# Brians_test_board_1_18.net
KiCad netlist of a schematic drawn in EAGLE
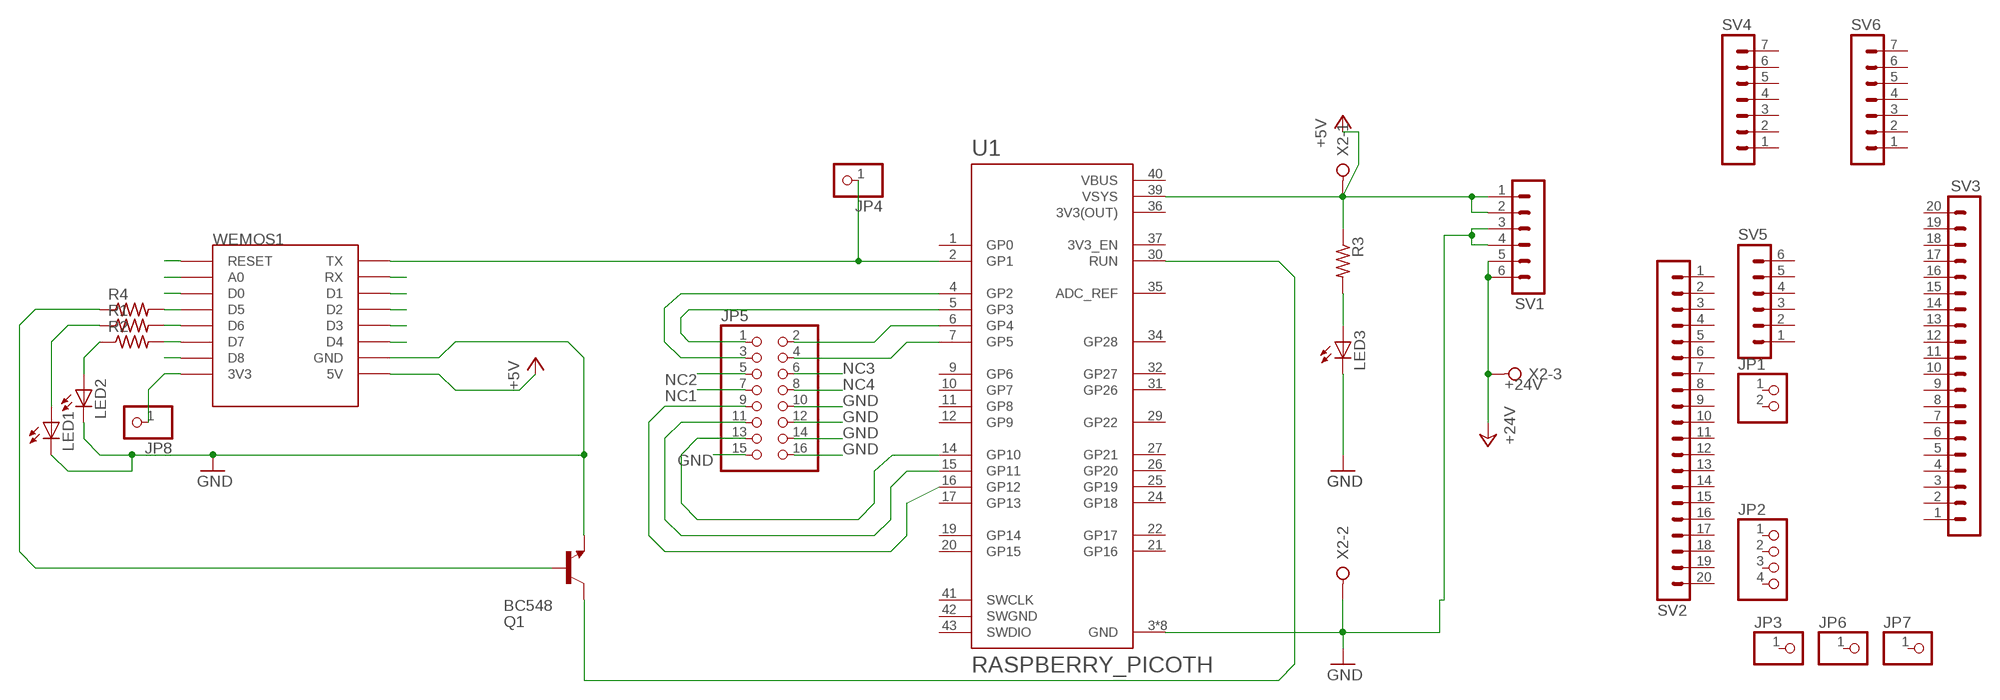
[diagram p0: schematic, sheet 1]

(export (version "E")
  (design (tool "Eeschema 10.0.6"))
  (components
    (comp (ref "JP1")
      (value "PINHD-1X2")
      (footprint "eagle-import:1X02")
      (libsource (lib "eagle-import") (part "PINHD-1X2"))
    )
    (comp (ref "JP2")
      (value "PINHD-1X4")
      (footprint "eagle-import:1X04")
      (libsource (lib "eagle-import") (part "PINHD-1X4"))
    )
    (comp (ref "JP3")
      (value "PINHD-1X1")
      (footprint "eagle-import:1X01")
      (libsource (lib "eagle-import") (part "PINHD-1X1"))
    )
    (comp (ref "JP4")
      (value "PINHD-1X1")
      (footprint "eagle-import:1X01")
      (libsource (lib "eagle-import") (part "PINHD-1X1"))
    )
    (comp (ref "JP5")
      (value "PINHD-2X8")
      (footprint "eagle-import:2X08")
      (libsource (lib "eagle-import") (part "PINHD-2X8"))
    )
    (comp (ref "JP6")
      (value "PINHD-1X1")
      (footprint "eagle-import:1X01")
      (libsource (lib "eagle-import") (part "PINHD-1X1"))
    )
    (comp (ref "JP7")
      (value "PINHD-1X1")
      (footprint "eagle-import:1X01")
      (libsource (lib "eagle-import") (part "PINHD-1X1"))
    )
    (comp (ref "JP8")
      (value "PINHD-1X1")
      (footprint "eagle-import:1X01")
      (libsource (lib "eagle-import") (part "PINHD-1X1"))
    )
    (comp (ref "LED1")
      (value "LED3MM")
      (footprint "eagle-import:LED3MM")
      (libsource (lib "eagle-import") (part "LED3MM"))
    )
    (comp (ref "LED2")
      (value "LED3MM")
      (footprint "eagle-import:LED3MM")
      (libsource (lib "eagle-import") (part "LED3MM"))
    )
    (comp (ref "LED3")
      (value "LED3MM")
      (footprint "eagle-import:LED3MM")
      (libsource (lib "eagle-import") (part "LED3MM"))
    )
    (comp (ref "Q1")
      (value "BC548")
      (footprint "eagle-import:TO92-EBC")
      (libsource (lib "eagle-import") (part "BC548"))
    )
    (comp (ref "R1")
      (value "R-US_0204/2V")
      (footprint "eagle-import:0204V")
      (libsource (lib "eagle-import") (part "R-US_0204/2V"))
    )
    (comp (ref "R2")
      (value "R-US_0204/2V")
      (footprint "eagle-import:0204V")
      (libsource (lib "eagle-import") (part "R-US_0204/2V"))
    )
    (comp (ref "R3")
      (value "R-US_0207/10")
      (footprint "eagle-import:0207_10")
      (libsource (lib "eagle-import") (part "R-US_0207/10"))
    )
    (comp (ref "R4")
      (value "R-US_0204/2V")
      (footprint "eagle-import:0204V")
      (libsource (lib "eagle-import") (part "R-US_0204/2V"))
    )
    (comp (ref "SV1")
      (value "MA06-1")
      (footprint "eagle-import:MA06-1")
      (libsource (lib "eagle-import") (part "MA06-1"))
    )
    (comp (ref "SV2")
      (value "MA20-1")
      (footprint "eagle-import:MA20-1")
      (libsource (lib "eagle-import") (part "MA20-1"))
    )
    (comp (ref "SV3")
      (value "MA20-1")
      (footprint "eagle-import:MA20-1")
      (libsource (lib "eagle-import") (part "MA20-1"))
    )
    (comp (ref "SV4")
      (value "MA07-1")
      (footprint "eagle-import:MA07-1")
      (libsource (lib "eagle-import") (part "MA07-1"))
    )
    (comp (ref "SV5")
      (value "MA06-1")
      (footprint "eagle-import:MA06-1")
      (libsource (lib "eagle-import") (part "MA06-1"))
    )
    (comp (ref "SV6")
      (value "MA07-1")
      (footprint "eagle-import:MA07-1")
      (libsource (lib "eagle-import") (part "MA07-1"))
    )
    (comp (ref "U1")
      (value "RASPBERRY_PICOTH")
      (footprint "eagle-import:PICO-PKG-TH")
      (libsource (lib "eagle-import") (part "RASPBERRY_PICOTH"))
    )
    (comp (ref "WEMOS1")
      (value "WEMOS-D1-MINI")
      (footprint "eagle-import:WEMOS-D1-MINI")
      (libsource (lib "eagle-import") (part "WEMOS-D1-MINI"))
    )
    (comp (ref "X2")
      (value "W237-3E")
      (footprint "eagle-import:W237-3E")
      (libsource (lib "eagle-import") (part "W237-3E"))
    )
  )
  (nets
    (net (code "1") (name "+5V") (class "Default")
      (node (ref "R3") (pin "1") (pinfunction "1_1") (pintype "passive"))
      (node (ref "SV1") (pin "1") (pinfunction "1_1") (pintype "passive"))
      (node (ref "SV1") (pin "2") (pinfunction "2_2") (pintype "passive"))
      (node (ref "U1") (pin "39") (pinfunction "VSYS_39") (pintype "power_in"))
      (node (ref "WEMOS1") (pin "5V") (pinfunction "5V_5V") (pintype "bidirectional"))
      (node (ref "X2") (pin "1") (pinfunction "KL_1") (pintype "passive"))
    )
    (net (code "2") (name "+24V") (class "Default")
      (node (ref "SV1") (pin "5") (pinfunction "5_5") (pintype "passive"))
      (node (ref "SV1") (pin "6") (pinfunction "6_6") (pintype "passive"))
      (node (ref "X2") (pin "3") (pinfunction "KL_3") (pintype "passive"))
    )
    (net (code "3") (name "/3V3(OUT)") (class "Default")
      (node (ref "U1") (pin "36") (pinfunction "3V3(OUT)_36") (pintype "power_in"))
    )
    (net (code "4") (name "/NC1") (class "Default")
      (node (ref "JP5") (pin "7") (pinfunction "7_7") (pintype "passive"))
    )
    (net (code "5") (name "/NC2") (class "Default")
      (node (ref "JP5") (pin "5") (pinfunction "5_5") (pintype "passive"))
    )
    (net (code "6") (name "/NC3") (class "Default")
      (node (ref "JP5") (pin "6") (pinfunction "6_6") (pintype "passive"))
    )
    (net (code "7") (name "/NC4") (class "Default")
      (node (ref "JP5") (pin "8") (pinfunction "8_8") (pintype "passive"))
    )
    (net (code "8") (name "/SWGND") (class "Default")
      (node (ref "U1") (pin "42") (pinfunction "SWGND_42") (pintype "power_in"))
    )
    (net (code "9") (name "/VBUS") (class "Default")
      (node (ref "U1") (pin "40") (pinfunction "VBUS_40") (pintype "power_in"))
    )
    (net (code "10") (name "GND") (class "Default")
      (node (ref "JP5") (pin "10") (pinfunction "10_10") (pintype "passive"))
      (node (ref "JP5") (pin "12") (pinfunction "12_12") (pintype "passive"))
      (node (ref "JP5") (pin "14") (pinfunction "14_14") (pintype "passive"))
      (node (ref "JP5") (pin "15") (pinfunction "15_15") (pintype "passive"))
      (node (ref "JP5") (pin "16") (pinfunction "16_16") (pintype "passive"))
      (node (ref "LED1") (pin "K") (pinfunction "C_K") (pintype "passive"))
      (node (ref "LED2") (pin "K") (pinfunction "C_K") (pintype "passive"))
      (node (ref "LED3") (pin "K") (pinfunction "C_K") (pintype "passive"))
      (node (ref "Q1") (pin "E") (pinfunction "E_E") (pintype "passive"))
      (node (ref "SV1") (pin "3") (pinfunction "3_3") (pintype "passive"))
      (node (ref "SV1") (pin "4") (pinfunction "4_4") (pintype "passive"))
      (node (ref "U1") (pin "13") (pinfunction "GND_13") (pintype "power_in"))
      (node (ref "U1") (pin "18") (pinfunction "GND_18") (pintype "power_in"))
      (node (ref "U1") (pin "23") (pinfunction "GND_23") (pintype "power_in"))
      (node (ref "U1") (pin "28") (pinfunction "GND_28") (pintype "power_in"))
      (node (ref "U1") (pin "3") (pinfunction "GND_3") (pintype "power_in"))
      (node (ref "U1") (pin "33") (pinfunction "GND_33") (pintype "power_in"))
      (node (ref "U1") (pin "38") (pinfunction "GND_38") (pintype "power_in"))
      (node (ref "U1") (pin "8") (pinfunction "GND_8") (pintype "power_in"))
      (node (ref "WEMOS1") (pin "GND") (pinfunction "GND_GND") (pintype "bidirectional"))
      (node (ref "X2") (pin "2") (pinfunction "KL_2") (pintype "passive"))
    )
    (net (code "11") (name "Net-(JP8-Pad1)") (class "Default")
      (node (ref "JP8") (pin "1") (pinfunction "1_1") (pintype "passive"))
      (node (ref "WEMOS1") (pin "3V3") (pinfunction "3V3_3V3") (pintype "bidirectional"))
    )
    (net (code "12") (name "Net-(LED1-PadA)") (class "Default")
      (node (ref "LED1") (pin "A") (pinfunction "A_A") (pintype "passive"))
      (node (ref "R1") (pin "1") (pinfunction "1_1") (pintype "passive"))
    )
    (net (code "13") (name "Net-(LED2-PadA)") (class "Default")
      (node (ref "LED2") (pin "A") (pinfunction "A_A") (pintype "passive"))
      (node (ref "R2") (pin "1") (pinfunction "1_1") (pintype "passive"))
    )
    (net (code "14") (name "Net-(LED3-PadA)") (class "Default")
      (node (ref "LED3") (pin "A") (pinfunction "A_A") (pintype "passive"))
      (node (ref "R3") (pin "2") (pinfunction "2_2") (pintype "passive"))
    )
    (net (code "15") (name "Net-(Q1-PadB)") (class "Default")
      (node (ref "Q1") (pin "B") (pinfunction "B_B") (pintype "passive"))
      (node (ref "R4") (pin "1") (pinfunction "1_1") (pintype "passive"))
    )
    (net (code "16") (name "Net-(R1-Pad2)") (class "Default")
      (node (ref "R1") (pin "2") (pinfunction "2_2") (pintype "passive"))
      (node (ref "WEMOS1") (pin "D6") (pinfunction "D6_D6") (pintype "bidirectional"))
    )
    (net (code "17") (name "Net-(R2-Pad2)") (class "Default")
      (node (ref "R2") (pin "2") (pinfunction "2_2") (pintype "passive"))
      (node (ref "WEMOS1") (pin "D7") (pinfunction "D7_D7") (pintype "bidirectional"))
    )
    (net (code "18") (name "Net-(R4-Pad2)") (class "Default")
      (node (ref "R4") (pin "2") (pinfunction "2_2") (pintype "passive"))
      (node (ref "WEMOS1") (pin "D5") (pinfunction "D5_D5") (pintype "bidirectional"))
    )
    (net (code "19") (name "Net-(U1-GP1)") (class "Default")
      (node (ref "JP4") (pin "1") (pinfunction "1_1") (pintype "passive"))
      (node (ref "U1") (pin "2") (pinfunction "GP1_2") (pintype "bidirectional"))
      (node (ref "WEMOS1") (pin "TX") (pinfunction "TX_TX") (pintype "bidirectional"))
    )
    (net (code "20") (name "Net-(U1-GP2)") (class "Default")
      (node (ref "JP5") (pin "3") (pinfunction "3_3") (pintype "passive"))
      (node (ref "U1") (pin "4") (pinfunction "GP2_4") (pintype "bidirectional"))
    )
    (net (code "21") (name "Net-(U1-GP3)") (class "Default")
      (node (ref "JP5") (pin "1") (pinfunction "1_1") (pintype "passive"))
      (node (ref "U1") (pin "5") (pinfunction "GP3_5") (pintype "bidirectional"))
    )
    (net (code "22") (name "Net-(U1-GP4)") (class "Default")
      (node (ref "JP5") (pin "2") (pinfunction "2_2") (pintype "passive"))
      (node (ref "U1") (pin "6") (pinfunction "GP4_6") (pintype "bidirectional"))
    )
    (net (code "23") (name "Net-(U1-GP5)") (class "Default")
      (node (ref "JP5") (pin "4") (pinfunction "4_4") (pintype "passive"))
      (node (ref "U1") (pin "7") (pinfunction "GP5_7") (pintype "bidirectional"))
    )
    (net (code "24") (name "Net-(U1-GP10)") (class "Default")
      (node (ref "JP5") (pin "13") (pinfunction "13_13") (pintype "passive"))
      (node (ref "U1") (pin "14") (pinfunction "GP10_14") (pintype "bidirectional"))
    )
    (net (code "25") (name "Net-(U1-GP11)") (class "Default")
      (node (ref "JP5") (pin "11") (pinfunction "11_11") (pintype "passive"))
      (node (ref "U1") (pin "15") (pinfunction "GP11_15") (pintype "bidirectional"))
    )
    (net (code "26") (name "Net-(U1-GP12)") (class "Default")
      (node (ref "JP5") (pin "9") (pinfunction "9_9") (pintype "passive"))
      (node (ref "U1") (pin "16") (pinfunction "GP12_16") (pintype "bidirectional"))
    )
    (net (code "27") (name "Net-(U1-RUN)") (class "Default")
      (node (ref "Q1") (pin "C") (pinfunction "C_C") (pintype "passive"))
      (node (ref "U1") (pin "30") (pinfunction "RUN_30") (pintype "input"))
    )
    (net (code "28") (name "unconnected-(JP1-Pad1)") (class "Default")
      (node (ref "JP1") (pin "1") (pinfunction "1_1") (pintype "passive"))
    )
    (net (code "29") (name "unconnected-(JP1-Pad2)") (class "Default")
      (node (ref "JP1") (pin "2") (pinfunction "2_2") (pintype "passive"))
    )
    (net (code "30") (name "unconnected-(JP2-Pad1)") (class "Default")
      (node (ref "JP2") (pin "1") (pinfunction "1_1") (pintype "passive"))
    )
    (net (code "31") (name "unconnected-(JP2-Pad2)") (class "Default")
      (node (ref "JP2") (pin "2") (pinfunction "2_2") (pintype "passive"))
    )
    (net (code "32") (name "unconnected-(JP2-Pad3)") (class "Default")
      (node (ref "JP2") (pin "3") (pinfunction "3_3") (pintype "passive"))
    )
    (net (code "33") (name "unconnected-(JP2-Pad4)") (class "Default")
      (node (ref "JP2") (pin "4") (pinfunction "4_4") (pintype "passive"))
    )
    (net (code "34") (name "unconnected-(JP3-Pad1)") (class "Default")
      (node (ref "JP3") (pin "1") (pinfunction "1_1") (pintype "passive"))
    )
    (net (code "35") (name "unconnected-(JP6-Pad1)") (class "Default")
      (node (ref "JP6") (pin "1") (pinfunction "1_1") (pintype "passive"))
    )
    (net (code "36") (name "unconnected-(JP7-Pad1)") (class "Default")
      (node (ref "JP7") (pin "1") (pinfunction "1_1") (pintype "passive"))
    )
    (net (code "37") (name "unconnected-(SV2-Pad1)") (class "Default")
      (node (ref "SV2") (pin "1") (pinfunction "1_1") (pintype "passive"))
    )
    (net (code "38") (name "unconnected-(SV2-Pad2)") (class "Default")
      (node (ref "SV2") (pin "2") (pinfunction "2_2") (pintype "passive"))
    )
    (net (code "39") (name "unconnected-(SV2-Pad3)") (class "Default")
      (node (ref "SV2") (pin "3") (pinfunction "3_3") (pintype "passive"))
    )
    (net (code "40") (name "unconnected-(SV2-Pad4)") (class "Default")
      (node (ref "SV2") (pin "4") (pinfunction "4_4") (pintype "passive"))
    )
    (net (code "41") (name "unconnected-(SV2-Pad5)") (class "Default")
      (node (ref "SV2") (pin "5") (pinfunction "5_5") (pintype "passive"))
    )
    (net (code "42") (name "unconnected-(SV2-Pad6)") (class "Default")
      (node (ref "SV2") (pin "6") (pinfunction "6_6") (pintype "passive"))
    )
    (net (code "43") (name "unconnected-(SV2-Pad7)") (class "Default")
      (node (ref "SV2") (pin "7") (pinfunction "7_7") (pintype "passive"))
    )
    (net (code "44") (name "unconnected-(SV2-Pad8)") (class "Default")
      (node (ref "SV2") (pin "8") (pinfunction "8_8") (pintype "passive"))
    )
    (net (code "45") (name "unconnected-(SV2-Pad9)") (class "Default")
      (node (ref "SV2") (pin "9") (pinfunction "9_9") (pintype "passive"))
    )
    (net (code "46") (name "unconnected-(SV2-Pad10)") (class "Default")
      (node (ref "SV2") (pin "10") (pinfunction "10_10") (pintype "passive"))
    )
    (net (code "47") (name "unconnected-(SV2-Pad11)") (class "Default")
      (node (ref "SV2") (pin "11") (pinfunction "11_11") (pintype "passive"))
    )
    (net (code "48") (name "unconnected-(SV2-Pad12)") (class "Default")
      (node (ref "SV2") (pin "12") (pinfunction "12_12") (pintype "passive"))
    )
    (net (code "49") (name "unconnected-(SV2-Pad13)") (class "Default")
      (node (ref "SV2") (pin "13") (pinfunction "13_13") (pintype "passive"))
    )
    (net (code "50") (name "unconnected-(SV2-Pad14)") (class "Default")
      (node (ref "SV2") (pin "14") (pinfunction "14_14") (pintype "passive"))
    )
    (net (code "51") (name "unconnected-(SV2-Pad15)") (class "Default")
      (node (ref "SV2") (pin "15") (pinfunction "15_15") (pintype "passive"))
    )
    (net (code "52") (name "unconnected-(SV2-Pad16)") (class "Default")
      (node (ref "SV2") (pin "16") (pinfunction "16_16") (pintype "passive"))
    )
    (net (code "53") (name "unconnected-(SV2-Pad17)") (class "Default")
      (node (ref "SV2") (pin "17") (pinfunction "17_17") (pintype "passive"))
    )
    (net (code "54") (name "unconnected-(SV2-Pad18)") (class "Default")
      (node (ref "SV2") (pin "18") (pinfunction "18_18") (pintype "passive"))
    )
    (net (code "55") (name "unconnected-(SV2-Pad19)") (class "Default")
      (node (ref "SV2") (pin "19") (pinfunction "19_19") (pintype "passive"))
    )
    (net (code "56") (name "unconnected-(SV2-Pad20)") (class "Default")
      (node (ref "SV2") (pin "20") (pinfunction "20_20") (pintype "passive"))
    )
    (net (code "57") (name "unconnected-(SV3-Pad1)") (class "Default")
      (node (ref "SV3") (pin "1") (pinfunction "1_1") (pintype "passive"))
    )
    (net (code "58") (name "unconnected-(SV3-Pad2)") (class "Default")
      (node (ref "SV3") (pin "2") (pinfunction "2_2") (pintype "passive"))
    )
    (net (code "59") (name "unconnected-(SV3-Pad3)") (class "Default")
      (node (ref "SV3") (pin "3") (pinfunction "3_3") (pintype "passive"))
    )
    (net (code "60") (name "unconnected-(SV3-Pad4)") (class "Default")
      (node (ref "SV3") (pin "4") (pinfunction "4_4") (pintype "passive"))
    )
    (net (code "61") (name "unconnected-(SV3-Pad5)") (class "Default")
      (node (ref "SV3") (pin "5") (pinfunction "5_5") (pintype "passive"))
    )
    (net (code "62") (name "unconnected-(SV3-Pad6)") (class "Default")
      (node (ref "SV3") (pin "6") (pinfunction "6_6") (pintype "passive"))
    )
    (net (code "63") (name "unconnected-(SV3-Pad7)") (class "Default")
      (node (ref "SV3") (pin "7") (pinfunction "7_7") (pintype "passive"))
    )
    (net (code "64") (name "unconnected-(SV3-Pad8)") (class "Default")
      (node (ref "SV3") (pin "8") (pinfunction "8_8") (pintype "passive"))
    )
    (net (code "65") (name "unconnected-(SV3-Pad9)") (class "Default")
      (node (ref "SV3") (pin "9") (pinfunction "9_9") (pintype "passive"))
    )
    (net (code "66") (name "unconnected-(SV3-Pad10)") (class "Default")
      (node (ref "SV3") (pin "10") (pinfunction "10_10") (pintype "passive"))
    )
    (net (code "67") (name "unconnected-(SV3-Pad11)") (class "Default")
      (node (ref "SV3") (pin "11") (pinfunction "11_11") (pintype "passive"))
    )
    (net (code "68") (name "unconnected-(SV3-Pad12)") (class "Default")
      (node (ref "SV3") (pin "12") (pinfunction "12_12") (pintype "passive"))
    )
    (net (code "69") (name "unconnected-(SV3-Pad13)") (class "Default")
      (node (ref "SV3") (pin "13") (pinfunction "13_13") (pintype "passive"))
    )
    (net (code "70") (name "unconnected-(SV3-Pad14)") (class "Default")
      (node (ref "SV3") (pin "14") (pinfunction "14_14") (pintype "passive"))
    )
    (net (code "71") (name "unconnected-(SV3-Pad15)") (class "Default")
      (node (ref "SV3") (pin "15") (pinfunction "15_15") (pintype "passive"))
    )
    (net (code "72") (name "unconnected-(SV3-Pad16)") (class "Default")
      (node (ref "SV3") (pin "16") (pinfunction "16_16") (pintype "passive"))
    )
    (net (code "73") (name "unconnected-(SV3-Pad17)") (class "Default")
      (node (ref "SV3") (pin "17") (pinfunction "17_17") (pintype "passive"))
    )
    (net (code "74") (name "unconnected-(SV3-Pad18)") (class "Default")
      (node (ref "SV3") (pin "18") (pinfunction "18_18") (pintype "passive"))
    )
    (net (code "75") (name "unconnected-(SV3-Pad19)") (class "Default")
      (node (ref "SV3") (pin "19") (pinfunction "19_19") (pintype "passive"))
    )
    (net (code "76") (name "unconnected-(SV3-Pad20)") (class "Default")
      (node (ref "SV3") (pin "20") (pinfunction "20_20") (pintype "passive"))
    )
    (net (code "77") (name "unconnected-(SV4-Pad1)") (class "Default")
      (node (ref "SV4") (pin "1") (pinfunction "1_1") (pintype "passive"))
    )
    (net (code "78") (name "unconnected-(SV4-Pad2)") (class "Default")
      (node (ref "SV4") (pin "2") (pinfunction "2_2") (pintype "passive"))
    )
    (net (code "79") (name "unconnected-(SV4-Pad3)") (class "Default")
      (node (ref "SV4") (pin "3") (pinfunction "3_3") (pintype "passive"))
    )
    (net (code "80") (name "unconnected-(SV4-Pad4)") (class "Default")
      (node (ref "SV4") (pin "4") (pinfunction "4_4") (pintype "passive"))
    )
    (net (code "81") (name "unconnected-(SV4-Pad5)") (class "Default")
      (node (ref "SV4") (pin "5") (pinfunction "5_5") (pintype "passive"))
    )
    (net (code "82") (name "unconnected-(SV4-Pad6)") (class "Default")
      (node (ref "SV4") (pin "6") (pinfunction "6_6") (pintype "passive"))
    )
    (net (code "83") (name "unconnected-(SV4-Pad7)") (class "Default")
      (node (ref "SV4") (pin "7") (pinfunction "7_7") (pintype "passive"))
    )
    (net (code "84") (name "unconnected-(SV5-Pad1)") (class "Default")
      (node (ref "SV5") (pin "1") (pinfunction "1_1") (pintype "passive"))
    )
    (net (code "85") (name "unconnected-(SV5-Pad2)") (class "Default")
      (node (ref "SV5") (pin "2") (pinfunction "2_2") (pintype "passive"))
    )
    (net (code "86") (name "unconnected-(SV5-Pad3)") (class "Default")
      (node (ref "SV5") (pin "3") (pinfunction "3_3") (pintype "passive"))
    )
    (net (code "87") (name "unconnected-(SV5-Pad4)") (class "Default")
      (node (ref "SV5") (pin "4") (pinfunction "4_4") (pintype "passive"))
    )
    (net (code "88") (name "unconnected-(SV5-Pad5)") (class "Default")
      (node (ref "SV5") (pin "5") (pinfunction "5_5") (pintype "passive"))
    )
    (net (code "89") (name "unconnected-(SV5-Pad6)") (class "Default")
      (node (ref "SV5") (pin "6") (pinfunction "6_6") (pintype "passive"))
    )
    (net (code "90") (name "unconnected-(SV6-Pad1)") (class "Default")
      (node (ref "SV6") (pin "1") (pinfunction "1_1") (pintype "passive"))
    )
    (net (code "91") (name "unconnected-(SV6-Pad2)") (class "Default")
      (node (ref "SV6") (pin "2") (pinfunction "2_2") (pintype "passive"))
    )
    (net (code "92") (name "unconnected-(SV6-Pad3)") (class "Default")
      (node (ref "SV6") (pin "3") (pinfunction "3_3") (pintype "passive"))
    )
    (net (code "93") (name "unconnected-(SV6-Pad4)") (class "Default")
      (node (ref "SV6") (pin "4") (pinfunction "4_4") (pintype "passive"))
    )
    (net (code "94") (name "unconnected-(SV6-Pad5)") (class "Default")
      (node (ref "SV6") (pin "5") (pinfunction "5_5") (pintype "passive"))
    )
    (net (code "95") (name "unconnected-(SV6-Pad6)") (class "Default")
      (node (ref "SV6") (pin "6") (pinfunction "6_6") (pintype "passive"))
    )
    (net (code "96") (name "unconnected-(SV6-Pad7)") (class "Default")
      (node (ref "SV6") (pin "7") (pinfunction "7_7") (pintype "passive"))
    )
    (net (code "97") (name "unconnected-(U1-3V3_EN-Pad37)") (class "Default")
      (node (ref "U1") (pin "37") (pinfunction "3V3_EN_37") (pintype "input"))
    )
    (net (code "98") (name "unconnected-(U1-ADC_REF-Pad35)") (class "Default")
      (node (ref "U1") (pin "35") (pinfunction "ADC_REF_35") (pintype "input"))
    )
    (net (code "99") (name "unconnected-(U1-GP0-Pad1)") (class "Default")
      (node (ref "U1") (pin "1") (pinfunction "GP0_1") (pintype "bidirectional"))
    )
    (net (code "100") (name "unconnected-(U1-GP6-Pad9)") (class "Default")
      (node (ref "U1") (pin "9") (pinfunction "GP6_9") (pintype "bidirectional"))
    )
    (net (code "101") (name "unconnected-(U1-GP7-Pad10)") (class "Default")
      (node (ref "U1") (pin "10") (pinfunction "GP7_10") (pintype "bidirectional"))
    )
    (net (code "102") (name "unconnected-(U1-GP8-Pad11)") (class "Default")
      (node (ref "U1") (pin "11") (pinfunction "GP8_11") (pintype "bidirectional"))
    )
    (net (code "103") (name "unconnected-(U1-GP9-Pad12)") (class "Default")
      (node (ref "U1") (pin "12") (pinfunction "GP9_12") (pintype "bidirectional"))
    )
    (net (code "104") (name "unconnected-(U1-GP13-Pad17)") (class "Default")
      (node (ref "U1") (pin "17") (pinfunction "GP13_17") (pintype "bidirectional"))
    )
    (net (code "105") (name "unconnected-(U1-GP14-Pad19)") (class "Default")
      (node (ref "U1") (pin "19") (pinfunction "GP14_19") (pintype "bidirectional"))
    )
    (net (code "106") (name "unconnected-(U1-GP15-Pad20)") (class "Default")
      (node (ref "U1") (pin "20") (pinfunction "GP15_20") (pintype "bidirectional"))
    )
    (net (code "107") (name "unconnected-(U1-GP16-Pad21)") (class "Default")
      (node (ref "U1") (pin "21") (pinfunction "GP16_21") (pintype "bidirectional"))
    )
    (net (code "108") (name "unconnected-(U1-GP17-Pad22)") (class "Default")
      (node (ref "U1") (pin "22") (pinfunction "GP17_22") (pintype "bidirectional"))
    )
    (net (code "109") (name "unconnected-(U1-GP18-Pad24)") (class "Default")
      (node (ref "U1") (pin "24") (pinfunction "GP18_24") (pintype "bidirectional"))
    )
    (net (code "110") (name "unconnected-(U1-GP19-Pad25)") (class "Default")
      (node (ref "U1") (pin "25") (pinfunction "GP19_25") (pintype "bidirectional"))
    )
    (net (code "111") (name "unconnected-(U1-GP20-Pad26)") (class "Default")
      (node (ref "U1") (pin "26") (pinfunction "GP20_26") (pintype "bidirectional"))
    )
    (net (code "112") (name "unconnected-(U1-GP21-Pad27)") (class "Default")
      (node (ref "U1") (pin "27") (pinfunction "GP21_27") (pintype "bidirectional"))
    )
    (net (code "113") (name "unconnected-(U1-GP22-Pad29)") (class "Default")
      (node (ref "U1") (pin "29") (pinfunction "GP22_29") (pintype "bidirectional"))
    )
    (net (code "114") (name "unconnected-(U1-GP26-Pad31)") (class "Default")
      (node (ref "U1") (pin "31") (pinfunction "GP26_31") (pintype "bidirectional"))
    )
    (net (code "115") (name "unconnected-(U1-GP27-Pad32)") (class "Default")
      (node (ref "U1") (pin "32") (pinfunction "GP27_32") (pintype "bidirectional"))
    )
    (net (code "116") (name "unconnected-(U1-GP28-Pad34)") (class "Default")
      (node (ref "U1") (pin "34") (pinfunction "GP28_34") (pintype "bidirectional"))
    )
    (net (code "117") (name "unconnected-(U1-SWCLK-Pad41)") (class "Default")
      (node (ref "U1") (pin "41") (pinfunction "SWCLK_41") (pintype "input"))
    )
    (net (code "118") (name "unconnected-(U1-SWDIO-Pad43)") (class "Default")
      (node (ref "U1") (pin "43") (pinfunction "SWDIO_43") (pintype "bidirectional"))
    )
    (net (code "119") (name "unconnected-(WEMOS1-PadA0)") (class "Default")
      (node (ref "WEMOS1") (pin "A0") (pinfunction "A0_A0") (pintype "bidirectional"))
    )
    (net (code "120") (name "unconnected-(WEMOS1-PadD0)") (class "Default")
      (node (ref "WEMOS1") (pin "D0") (pinfunction "D0_D0") (pintype "bidirectional"))
    )
    (net (code "121") (name "unconnected-(WEMOS1-PadD1)") (class "Default")
      (node (ref "WEMOS1") (pin "D1") (pinfunction "D1_D1") (pintype "bidirectional"))
    )
    (net (code "122") (name "unconnected-(WEMOS1-PadD2)") (class "Default")
      (node (ref "WEMOS1") (pin "D2") (pinfunction "D2_D2") (pintype "bidirectional"))
    )
    (net (code "123") (name "unconnected-(WEMOS1-PadD3)") (class "Default")
      (node (ref "WEMOS1") (pin "D3") (pinfunction "D3_D3") (pintype "bidirectional"))
    )
    (net (code "124") (name "unconnected-(WEMOS1-PadD4)") (class "Default")
      (node (ref "WEMOS1") (pin "D4") (pinfunction "D4_D4") (pintype "bidirectional"))
    )
    (net (code "125") (name "unconnected-(WEMOS1-PadD8)") (class "Default")
      (node (ref "WEMOS1") (pin "D8") (pinfunction "D8_D8") (pintype "bidirectional"))
    )
    (net (code "126") (name "unconnected-(WEMOS1-PadRESET)") (class "Default")
      (node (ref "WEMOS1") (pin "RESET") (pinfunction "RESET_RESET") (pintype "bidirectional"))
    )
    (net (code "127") (name "unconnected-(WEMOS1-PadRX)") (class "Default")
      (node (ref "WEMOS1") (pin "RX") (pinfunction "RX_RX") (pintype "bidirectional"))
    )
  )
)
